# ProDocument_Schematics_2024-05-18.net
KiCad netlist of a schematic drawn in EasyEDA Pro
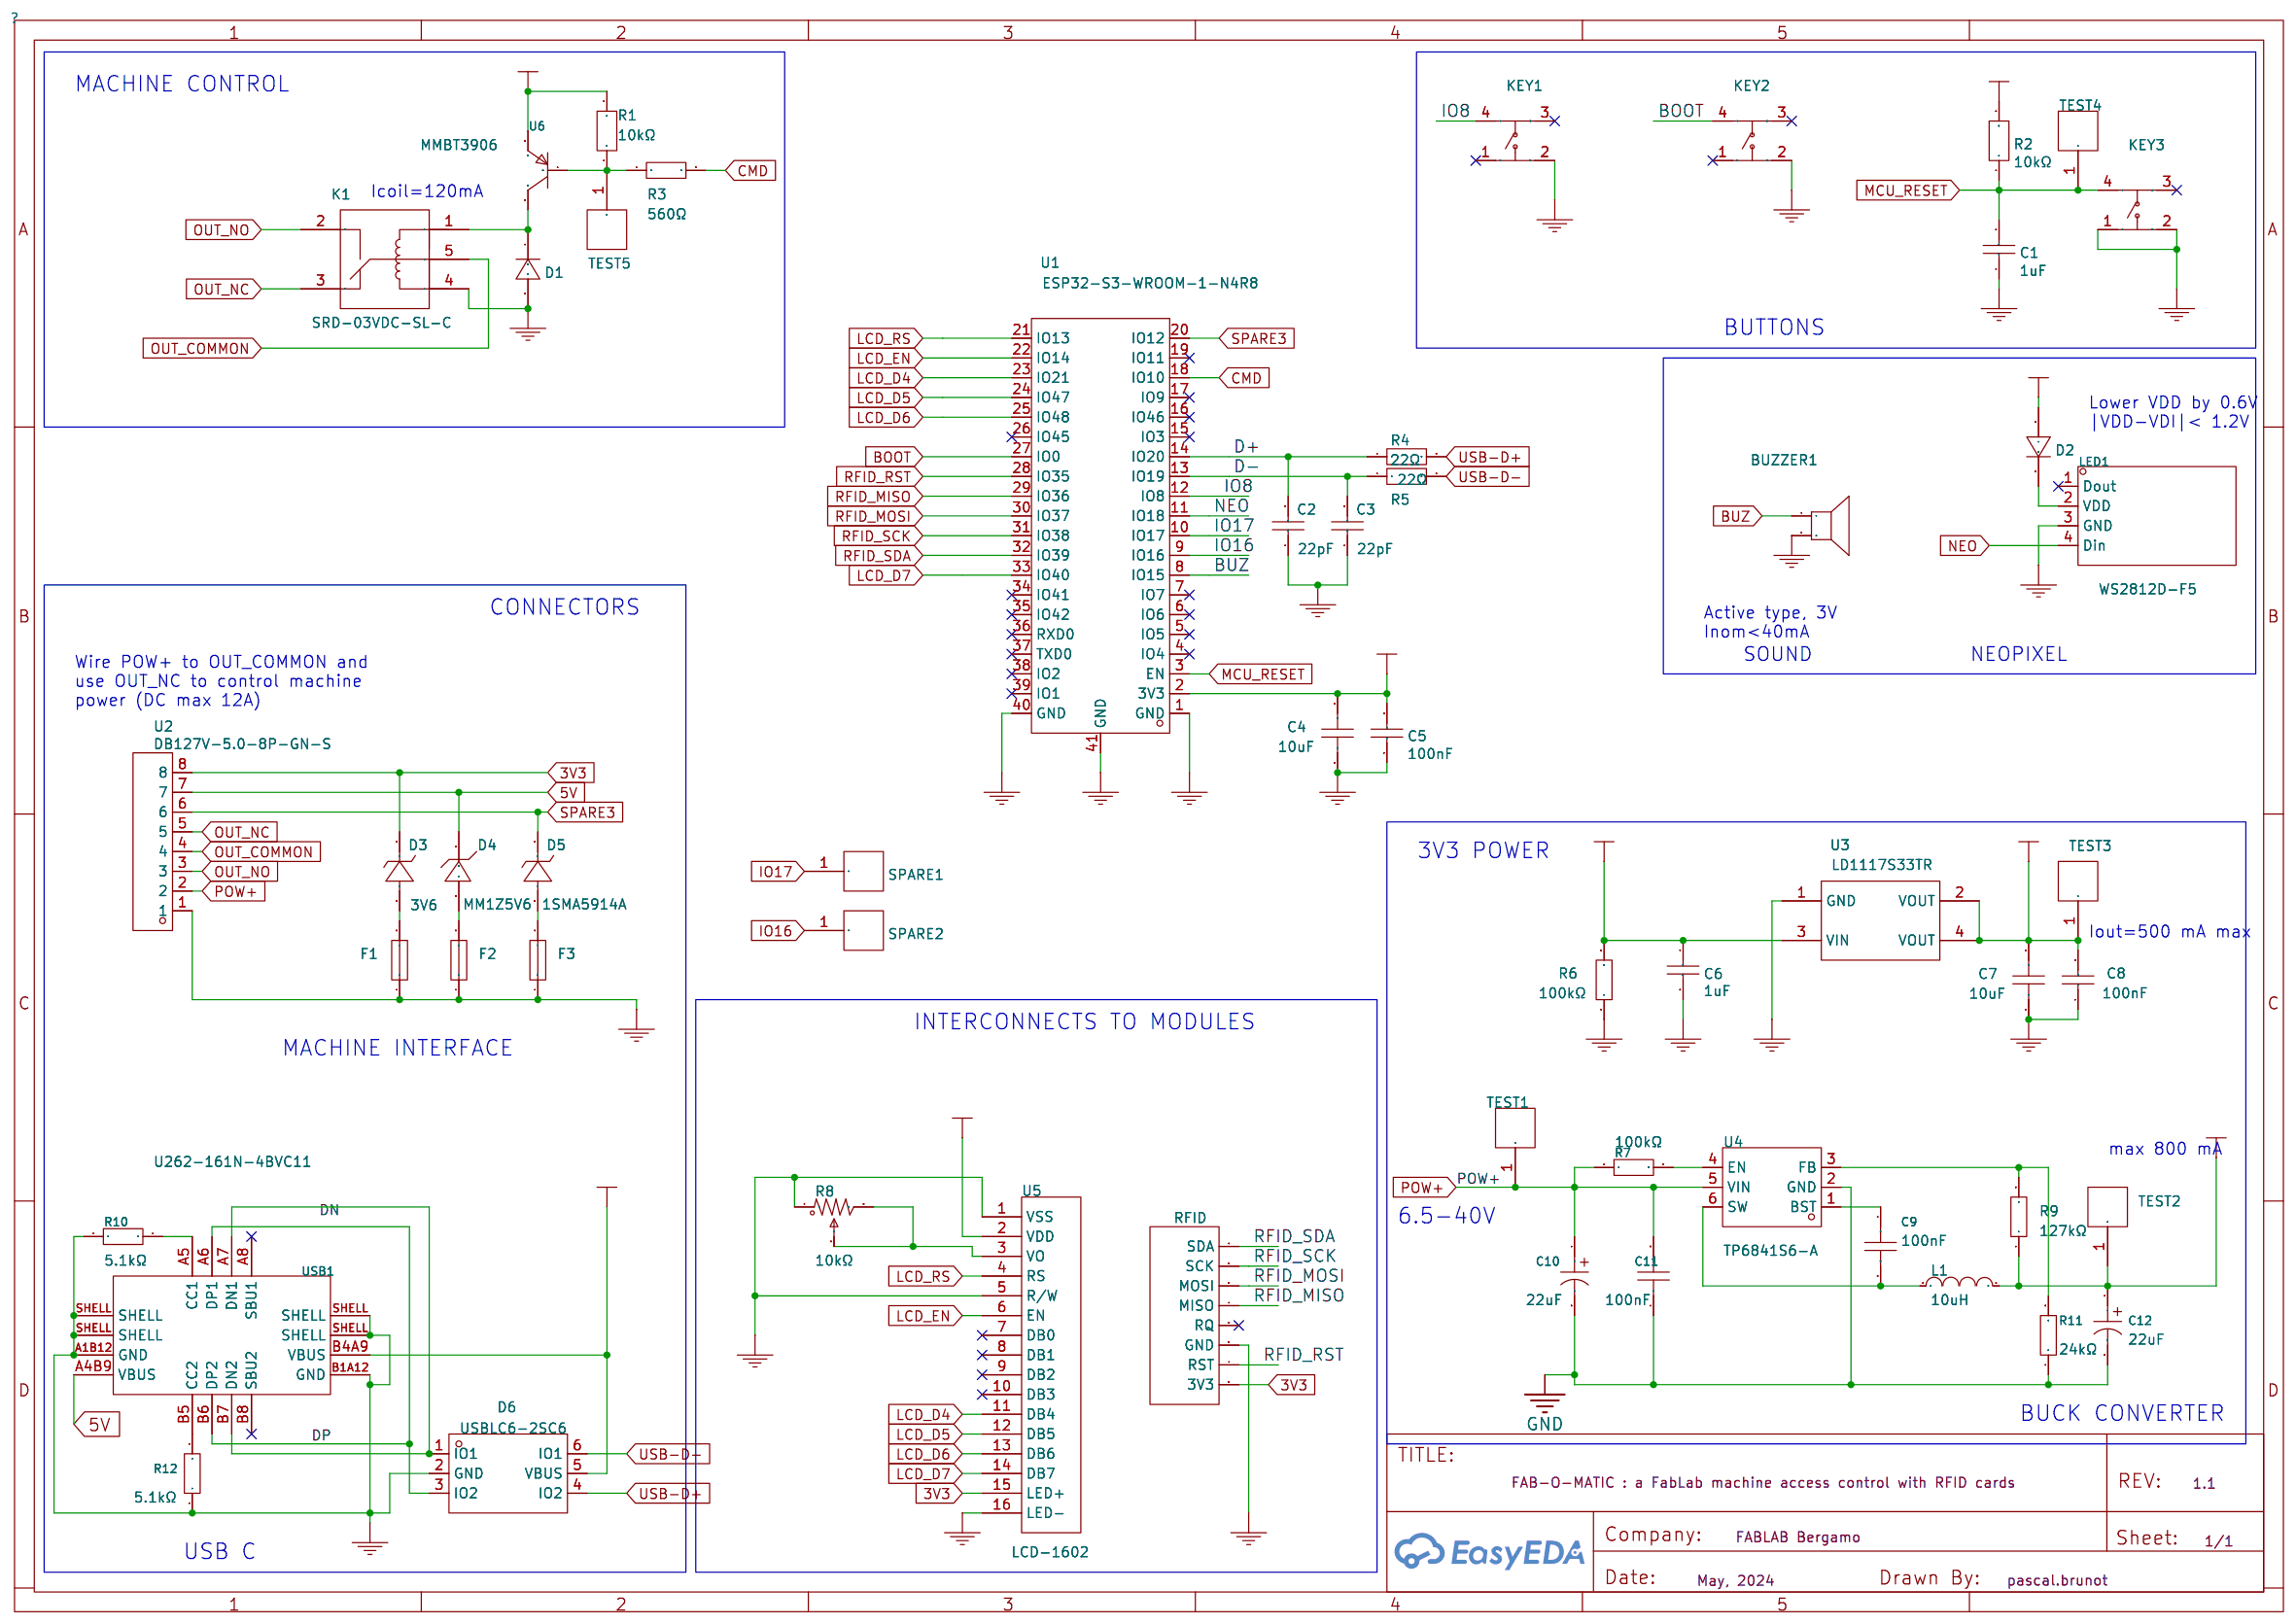
[diagram p0: schematic sheet]

(export (version "E")
  (design (tool "Eeschema 10.0.6"))
  (components
    (comp (ref "BUZZER1")
      (value "4kHz")
      (fields (field (name "Manufacturer Part") "SFN-12055PA6.5") (field (name "Manufacturer") "S&S(海旭)"))
      (libsource (lib "easyedapro") (part "4000Hz"))
    )
    (comp (ref "C1")
      (value "1uF")
      (fields
        (field (name "Manufacturer Part") "CL21B105KBFNNNE")
        (field (name "Manufacturer") "SAMSUNG(三星)")
      )
      (libsource (lib "easyedapro") (part "1uF"))
    )
    (comp (ref "C2")
      (value "22pF")
      (fields
        (field (name "Manufacturer Part") "CL10C220JB8NNNC")
        (field (name "Manufacturer") "SAMSUNG(三星)")
      )
      (libsource (lib "easyedapro") (part "22pF"))
    )
    (comp (ref "C3")
      (value "22pF")
      (fields
        (field (name "Manufacturer Part") "CL10C220JB8NNNC")
        (field (name "Manufacturer") "SAMSUNG(三星)")
      )
      (libsource (lib "easyedapro") (part "22pF"))
    )
    (comp (ref "C4")
      (value "10uF")
      (fields
        (field (name "Manufacturer Part") "GRM21BR61H106KE43L")
        (field (name "Manufacturer") "muRata(村田)")
      )
      (libsource (lib "easyedapro") (part "10uF"))
    )
    (comp (ref "C5")
      (value "100nF")
      (fields
        (field (name "Manufacturer Part") "CL21B104KCFNNNE")
        (field (name "Manufacturer") "SAMSUNG(三星)")
      )
      (libsource (lib "easyedapro") (part "100nF"))
    )
    (comp (ref "C6")
      (value "1uF")
      (fields
        (field (name "Manufacturer Part") "CL21B105KBFNNNE")
        (field (name "Manufacturer") "SAMSUNG(三星)")
      )
      (libsource (lib "easyedapro") (part "1uF"))
    )
    (comp (ref "C7")
      (value "10uF")
      (fields
        (field (name "Manufacturer Part") "GRM21BR61H106KE43L")
        (field (name "Manufacturer") "muRata(村田)")
      )
      (libsource (lib "easyedapro") (part "10uF"))
    )
    (comp (ref "C8")
      (value "100nF")
      (fields
        (field (name "Manufacturer Part") "CL21B104KCFNNNE")
        (field (name "Manufacturer") "SAMSUNG(三星)")
      )
      (libsource (lib "easyedapro") (part "100nF"))
    )
    (comp (ref "C9")
      (value "100nF")
      (footprint "easyedapro:C0603")
      (fields
        (field (name "Manufacturer Part") "CC0603KRX7R9BB104")
        (field (name "Manufacturer") "YAGEO(国巨)")
      )
      (libsource (lib "easyedapro") (part "CC0603KRX7R9BB104"))
    )
    (comp (ref "C10")
      (value "22uF")
      (footprint "easyedapro:CAP-SMD_BD6.3-L6.6-W6.6-FD")
      (fields
        (field (name "Manufacturer Part") "RVT22UF50V67RV0028")
        (field (name "Manufacturer") "KNSCHA(科尼盛)")
      )
      (libsource (lib "easyedapro") (part "RVT22UF50V67RV0028"))
    )
    (comp (ref "C11")
      (value "100nF")
      (footprint "easyedapro:C0603")
      (fields
        (field (name "Manufacturer Part") "CC0603KRX7R9BB104")
        (field (name "Manufacturer") "YAGEO(国巨)")
      )
      (libsource (lib "easyedapro") (part "CC0603KRX7R9BB104"))
    )
    (comp (ref "C12")
      (value "22uF")
      (footprint "easyedapro:CAP-SMD_BD6.3-L6.6-W6.6-FD")
      (fields
        (field (name "Manufacturer Part") "RVT22UF50V67RV0028")
        (field (name "Manufacturer") "KNSCHA(科尼盛)")
      )
      (libsource (lib "easyedapro") (part "RVT22UF50V67RV0028"))
    )
    (comp (ref "D1")
      (value "SM4007PL")
      (fields (field (name "Manufacturer") "MDD"))
      (libsource (lib "easyedapro") (part "SM4007PL"))
    )
    (comp (ref "D2")
      (value "SM4007PL")
      (fields (field (name "Manufacturer") "MDD"))
      (libsource (lib "easyedapro") (part "SM4007PL"))
    )
    (comp (ref "D3")
      (value "3V6")
      (fields (field (name "Manufacturer") "LGE(鲁光)"))
      (libsource (lib "easyedapro") (part "3V6"))
    )
    (comp (ref "D4")
      (value "MM1Z5V6")
      (fields (field (name "Manufacturer") "ST(先科)"))
      (libsource (lib "easyedapro") (part "5V6"))
    )
    (comp (ref "D5")
      (value "1SMA5914A")
      (fields (field (name "Manufacturer") "LGE(鲁光)"))
      (libsource (lib "easyedapro") (part "3V6"))
    )
    (comp (ref "D6")
      (value "USBLC6-2SC6")
      (fields (field (name "Manufacturer") "TECH PUBLIC(台舟)"))
      (libsource (lib "easyedapro") (part "USBLC6"))
    )
    (comp (ref "F1")
      (value "1206L016WR")
      (fields (field (name "Manufacturer") "Littelfuse(美国力特)"))
      (libsource (lib "easyedapro") (part "1206L016WR"))
    )
    (comp (ref "F2")
      (value "1206L016WR")
      (fields (field (name "Manufacturer") "Littelfuse(美国力特)"))
      (libsource (lib "easyedapro") (part "1206L016WR"))
    )
    (comp (ref "F3")
      (value "1206L016WR")
      (fields (field (name "Manufacturer") "Littelfuse(美国力特)"))
      (libsource (lib "easyedapro") (part "1206L016WR"))
    )
    (comp (ref "K1")
      (value "SRD-03VDC-SL-C")
      (fields (field (name "Manufacturer") "松乐"))
      (libsource (lib "easyedapro") (part "SRD-03VDC-SL-C_C496430"))
    )
    (comp (ref "KEY1")
      (value "TSA063G60-250")
      (footprint "easyedapro:KEY-SMD_4P-L6.1-W6.1-P4.50-LS9.0")
      (fields (field (name "Manufacturer") "BRIGHT(博瑞泰)"))
      (libsource (lib "easyedapro") (part "TSA063G60-250"))
    )
    (comp (ref "KEY2")
      (value "TSA063G60-250")
      (footprint "easyedapro:KEY-SMD_4P-L6.1-W6.1-P4.50-LS9.0")
      (fields (field (name "Manufacturer") "BRIGHT(博瑞泰)"))
      (libsource (lib "easyedapro") (part "TSA063G60-250"))
    )
    (comp (ref "KEY3")
      (value "TSA063G60-250")
      (footprint "easyedapro:KEY-SMD_4P-L6.1-W6.1-P4.50-LS9.0")
      (fields (field (name "Manufacturer") "BRIGHT(博瑞泰)"))
      (libsource (lib "easyedapro") (part "TSA063G60-250"))
    )
    (comp (ref "L1")
      (value "10uH")
      (footprint "easyedapro:IND-SMD_L4.0-W4.0")
      (fields (field (name "Manufacturer Part") "SWPA4030S100MT") (field (name "Manufacturer") "Sunlord(顺络)"))
      (libsource (lib "easyedapro") (part "SWPA4030S100MT"))
    )
    (comp (ref "LED1")
      (value "WS2812D-F5")
      (footprint "easyedapro:LED-TH_4P-BD5.8-P1.30")
      (description "Lamp Holder Type:5mm圆形灯头")
      (fields (field (name "Manufacturer") "worldsemi"))
      (libsource (lib "easyedapro") (part "WS2812D-F5"))
    )
    (comp (ref "P1")
      (value "RFID")
      (footprint "easyedapro:footprint_17af")
      (fields
        (field (name "Manufacturer Part") "Female headerHDR1X8-2.54")
        (field (name "Manufacturer") "BOOMELE")
      )
      (libsource (lib "easyedapro") (part "RFID"))
    )
    (comp (ref "R1")
      (value "10kΩ")
      (fields
        (field (name "Manufacturer Part") "0805W8F1002T5E")
        (field (name "Manufacturer") "UNI-ROYAL(厚声)")
      )
      (libsource (lib "easyedapro") (part "10k"))
    )
    (comp (ref "R2")
      (value "10kΩ")
      (fields
        (field (name "Manufacturer Part") "0805W8F1002T5E")
        (field (name "Manufacturer") "UNI-ROYAL(厚声)")
      )
      (libsource (lib "easyedapro") (part "10k"))
    )
    (comp (ref "R3")
      (value "560Ω")
      (fields
        (field (name "Manufacturer Part") "0805W8F5600T5E")
        (field (name "Manufacturer") "UNI-ROYAL(厚声)")
      )
      (libsource (lib "easyedapro") (part "560Ω"))
    )
    (comp (ref "R4")
      (value "22Ω")
      (fields
        (field (name "Manufacturer Part") "0603WAF220JT5E")
        (field (name "Manufacturer") "UNI-ROYAL(厚声)")
      )
      (libsource (lib "easyedapro") (part "22"))
    )
    (comp (ref "R5")
      (value "22Ω")
      (fields
        (field (name "Manufacturer Part") "0603WAF220JT5E")
        (field (name "Manufacturer") "UNI-ROYAL(厚声)")
      )
      (libsource (lib "easyedapro") (part "22"))
    )
    (comp (ref "R6")
      (value "100kΩ")
      (fields
        (field (name "Manufacturer Part") "0805W8F1003T5E")
        (field (name "Manufacturer") "UNI-ROYAL(厚声)")
      )
      (libsource (lib "easyedapro") (part "100kΩ"))
    )
    (comp (ref "R7")
      (value "100kΩ")
      (footprint "easyedapro:R0603")
      (fields
        (field (name "Manufacturer Part") "0603WAF1003T5E")
        (field (name "Manufacturer") "UNI-ROYAL(厚声)")
      )
      (libsource (lib "easyedapro") (part "0603WAF1003T5E"))
    )
    (comp (ref "R8")
      (value "10kΩ")
      (footprint "easyedapro:RES-ADJ-TH_3362P")
      (description "Resistance: Tolerance:±10% Tolerance:±10%")
      (fields (field (name "Manufacturer Part") "3362P-1-103") (field (name "Manufacturer") "BOCHEN(博晨)"))
      (libsource (lib "easyedapro") (part "3362P-1-103_C118956"))
    )
    (comp (ref "R9")
      (value "127kΩ")
      (footprint "easyedapro:R0603")
      (fields (field (name "Manufacturer Part") "RC0603FR-07127KL") (field (name "Manufacturer") "YAGEO(国巨)"))
      (libsource (lib "easyedapro") (part "RC0603FR-07127KL"))
    )
    (comp (ref "R10")
      (value "5.1kΩ")
      (footprint "easyedapro:R0603")
      (fields
        (field (name "Manufacturer Part") "0603WAF5101T5E")
        (field (name "Manufacturer") "UNI-ROYAL(厚声)")
      )
      (libsource (lib "easyedapro") (part "0603WAF5101T5E"))
    )
    (comp (ref "R11")
      (value "24kΩ")
      (footprint "easyedapro:R0603")
      (fields
        (field (name "Manufacturer Part") "0603WAF2402T5E")
        (field (name "Manufacturer") "UNI-ROYAL(厚声)")
      )
      (libsource (lib "easyedapro") (part "0603WAF2402T5E"))
    )
    (comp (ref "R12")
      (value "5.1kΩ")
      (footprint "easyedapro:R0603")
      (fields
        (field (name "Manufacturer Part") "0603WAF5101T5E")
        (field (name "Manufacturer") "UNI-ROYAL(厚声)")
      )
      (libsource (lib "easyedapro") (part "0603WAF5101T5E"))
    )
    (comp (ref "SPARE1")
      (value "0577-0-43-80-21-27-10-0")
      (footprint "easyedapro:footprint_662d")
      (libsource (lib "easyedapro") (part "0577-0-43-80-21-27-10-0"))
    )
    (comp (ref "SPARE2")
      (value "0577-0-43-80-21-27-10-0")
      (footprint "easyedapro:footprint_662d")
      (libsource (lib "easyedapro") (part "0577-0-43-80-21-27-10-0"))
    )
    (comp (ref "TEST1")
      (value "0577-0-43-80-21-27-10-0")
      (footprint "easyedapro:footprint_662d")
      (libsource (lib "easyedapro") (part "0577-0-43-80-21-27-10-0"))
    )
    (comp (ref "TEST2")
      (value "0577-0-43-80-21-27-10-0")
      (footprint "easyedapro:footprint_662d")
      (libsource (lib "easyedapro") (part "0577-0-43-80-21-27-10-0"))
    )
    (comp (ref "TEST3")
      (value "0577-0-43-80-21-27-10-0")
      (footprint "easyedapro:footprint_662d")
      (libsource (lib "easyedapro") (part "0577-0-43-80-21-27-10-0"))
    )
    (comp (ref "TEST4")
      (value "0577-0-43-80-21-27-10-0")
      (footprint "easyedapro:footprint_662d")
      (libsource (lib "easyedapro") (part "0577-0-43-80-21-27-10-0"))
    )
    (comp (ref "TEST5")
      (value "0577-0-43-80-21-27-10-0")
      (footprint "easyedapro:footprint_662d")
      (libsource (lib "easyedapro") (part "0577-0-43-80-21-27-10-0"))
    )
    (comp (ref "U1")
      (value "ESP32-S3-WROOM-1-N4R8")
      (fields (field (name "Manufacturer") "ESPRESSIF(乐鑫)"))
      (libsource (lib "easyedapro") (part "ESP32-S3-WROOM-1-N4"))
    )
    (comp (ref "U2")
      (value "DB127V-5.0-8P-GN-S")
      (fields (field (name "Manufacturer") "DORABO(地博电气)"))
      (libsource (lib "easyedapro") (part "DB127V-5.0-8P-GN-S"))
    )
    (comp (ref "U3")
      (value "LD1117S33TR")
      (fields (field (name "Manufacturer") "ST(意法半导体)"))
      (libsource (lib "easyedapro") (part "LD1117S33TR"))
    )
    (comp (ref "U4")
      (value "TP6841S6-A")
      (footprint "easyedapro:SOT-23-6_L2.9-W1.6-P0.95-LS2.8-BL")
      (fields (field (name "Manufacturer") "TECH PUBLIC(台舟)"))
      (libsource (lib "easyedapro") (part "TP6841S6-A"))
    )
    (comp (ref "U5")
      (value "LCD-1602")
      (footprint "easyedapro:footprint_8a57")
      (fields (field (name "Manufacturer Part") "?"))
      (libsource (lib "easyedapro") (part "LCD-1602"))
    )
    (comp (ref "U6")
      (value "MMBT3906")
      (footprint "easyedapro:SOT-23-3_L2.9-W1.3-P1.90-LS2.4-BR")
      (fields (field (name "Manufacturer") "宏迦橙"))
      (libsource (lib "easyedapro") (part "MMBT3906_C7420354"))
    )
    (comp (ref "USB1")
      (value "U262-161N-4BVC11")
      (footprint "easyedapro:USB-3.1-SMD_U262-161N-4BVC11")
      (fields (field (name "Manufacturer") "XKB Connectivity(中国星坤)"))
      (libsource (lib "easyedapro") (part "U262-16XN-4BVC11"))
    )
  )
  (nets
    (net (code "1") (name "/D+") (class "Default")
      (node (ref "C2") (pin "2") (pinfunction "2_2") (pintype "input"))
      (node (ref "R4") (pin "1") (pinfunction "1_1") (pintype "input"))
      (node (ref "U1") (pin "14") (pinfunction "IO20_14") (pintype "unspecified"))
    )
    (net (code "2") (name "/D-") (class "Default")
      (node (ref "C3") (pin "2") (pinfunction "2_2") (pintype "input"))
      (node (ref "R5") (pin "1") (pinfunction "1_1") (pintype "input"))
      (node (ref "U1") (pin "13") (pinfunction "IO19_13") (pintype "unspecified"))
    )
    (net (code "3") (name "/DN") (class "Default")
      (node (ref "D6") (pin "1") (pinfunction "IO1_1") (pintype "unspecified"))
      (node (ref "USB1") (pin "A7") (pinfunction "DN1_A7") (pintype "input"))
      (node (ref "USB1") (pin "B7") (pinfunction "DN2_B7") (pintype "input"))
    )
    (net (code "4") (name "/DP") (class "Default")
      (node (ref "D6") (pin "3") (pinfunction "IO2_3") (pintype "unspecified"))
      (node (ref "USB1") (pin "A6") (pinfunction "DP1_A6") (pintype "input"))
      (node (ref "USB1") (pin "B6") (pinfunction "DP2_B6") (pintype "input"))
    )
    (net (code "5") (name "/IO8") (class "Default")
      (node (ref "KEY1") (pin "4") (pinfunction "4_4") (pintype "input"))
      (node (ref "U1") (pin "12") (pinfunction "IO8_12") (pintype "unspecified"))
    )
    (net (code "6") (name "3V3") (class "Default")
      (node (ref "C4") (pin "2") (pinfunction "2_2") (pintype "unspecified"))
      (node (ref "C5") (pin "2") (pinfunction "2_2") (pintype "input"))
      (node (ref "C7") (pin "2") (pinfunction "2_2") (pintype "unspecified"))
      (node (ref "C8") (pin "2") (pinfunction "2_2") (pintype "input"))
      (node (ref "D3") (pin "1") (pinfunction "C_1") (pintype "unspecified"))
      (node (ref "P1") (pin "8") (pinfunction "3V3_8") (pintype "input"))
      (node (ref "R1") (pin "2") (pinfunction "2_2") (pintype "unspecified"))
      (node (ref "R2") (pin "2") (pinfunction "2_2") (pintype "unspecified"))
      (node (ref "TEST3") (pin "1") (pinfunction "1_1") (pintype "unspecified"))
      (node (ref "U1") (pin "2") (pinfunction "3V3_2") (pintype "unspecified"))
      (node (ref "U2") (pin "8") (pinfunction "8_8") (pintype "unspecified"))
      (node (ref "U3") (pin "2") (pinfunction "VOUT_2") (pintype "unspecified"))
      (node (ref "U3") (pin "4") (pinfunction "VOUT_4") (pintype "unspecified"))
      (node (ref "U5") (pin "15") (pinfunction "LED+_15") (pintype "unspecified"))
      (node (ref "U6") (pin "2") (pinfunction "E_2") (pintype "input"))
    )
    (net (code "7") (name "5V") (class "Default")
      (node (ref "C12") (pin "1") (pinfunction "1_1") (pintype "input"))
      (node (ref "C6") (pin "1") (pinfunction "1_1") (pintype "input"))
      (node (ref "D2") (pin "2") (pinfunction "A_2") (pintype "unspecified"))
      (node (ref "D4") (pin "1") (pinfunction "C_1") (pintype "unspecified"))
      (node (ref "D6") (pin "5") (pinfunction "VBUS_5") (pintype "unspecified"))
      (node (ref "L1") (pin "2") (pinfunction "2_2") (pintype "input"))
      (node (ref "R6") (pin "2") (pinfunction "2_2") (pintype "unspecified"))
      (node (ref "R9") (pin "1") (pinfunction "1_1") (pintype "unspecified"))
      (node (ref "TEST2") (pin "1") (pinfunction "1_1") (pintype "unspecified"))
      (node (ref "U2") (pin "7") (pinfunction "7_7") (pintype "unspecified"))
      (node (ref "U3") (pin "3") (pinfunction "VIN_3") (pintype "unspecified"))
      (node (ref "U5") (pin "2") (pinfunction "VDD_2") (pintype "unspecified"))
      (node (ref "USB1") (pin "A4B9") (pinfunction "VBUS_A4B9") (pintype "input"))
      (node (ref "USB1") (pin "B4A9") (pinfunction "VBUS_B4A9") (pintype "input"))
    )
    (net (code "8") (name "BOOT") (class "Default")
      (node (ref "KEY2") (pin "4") (pinfunction "4_4") (pintype "input"))
      (node (ref "U1") (pin "27") (pinfunction "IO0_27") (pintype "unspecified"))
    )
    (net (code "9") (name "BUZ") (class "Default")
      (node (ref "BUZZER1") (pin "1") (pinfunction "1_1") (pintype "unspecified"))
      (node (ref "U1") (pin "8") (pinfunction "IO15_8") (pintype "unspecified"))
    )
    (net (code "10") (name "CMD") (class "Default")
      (node (ref "R3") (pin "2") (pinfunction "2_2") (pintype "input"))
      (node (ref "U1") (pin "18") (pinfunction "IO10_18") (pintype "unspecified"))
    )
    (net (code "11") (name "GND") (class "Default")
      (node (ref "BUZZER1") (pin "2") (pinfunction "2_2") (pintype "unspecified"))
      (node (ref "C1") (pin "1") (pinfunction "1_1") (pintype "input"))
      (node (ref "C10") (pin "2") (pinfunction "2_2") (pintype "input"))
      (node (ref "C11") (pin "1") (pinfunction "1_1") (pintype "input"))
      (node (ref "C12") (pin "2") (pinfunction "2_2") (pintype "input"))
      (node (ref "C2") (pin "1") (pinfunction "1_1") (pintype "input"))
      (node (ref "C3") (pin "1") (pinfunction "1_1") (pintype "input"))
      (node (ref "C4") (pin "1") (pinfunction "1_1") (pintype "unspecified"))
      (node (ref "C5") (pin "1") (pinfunction "1_1") (pintype "input"))
      (node (ref "C6") (pin "2") (pinfunction "2_2") (pintype "input"))
      (node (ref "C7") (pin "1") (pinfunction "1_1") (pintype "unspecified"))
      (node (ref "C8") (pin "1") (pinfunction "1_1") (pintype "input"))
      (node (ref "D1") (pin "2") (pinfunction "A_2") (pintype "unspecified"))
      (node (ref "D6") (pin "2") (pinfunction "GND_2") (pintype "unspecified"))
      (node (ref "F1") (pin "1") (pinfunction "1_1") (pintype "unspecified"))
      (node (ref "F2") (pin "1") (pinfunction "1_1") (pintype "unspecified"))
      (node (ref "F3") (pin "1") (pinfunction "1_1") (pintype "unspecified"))
      (node (ref "K1") (pin "4") (pinfunction "4_4") (pintype "unspecified"))
      (node (ref "KEY1") (pin "2") (pinfunction "2_2") (pintype "input"))
      (node (ref "KEY2") (pin "2") (pinfunction "2_2") (pintype "input"))
      (node (ref "KEY3") (pin "1") (pinfunction "1_1") (pintype "input"))
      (node (ref "KEY3") (pin "2") (pinfunction "2_2") (pintype "input"))
      (node (ref "LED1") (pin "3") (pinfunction "GND_3") (pintype "input"))
      (node (ref "P1") (pin "6") (pinfunction "GND_6") (pintype "input"))
      (node (ref "R10") (pin "2") (pinfunction "2_2") (pintype "input"))
      (node (ref "R11") (pin "1") (pinfunction "1_1") (pintype "input"))
      (node (ref "R12") (pin "1") (pinfunction "1_1") (pintype "input"))
      (node (ref "R6") (pin "1") (pinfunction "1_1") (pintype "unspecified"))
      (node (ref "R8") (pin "1") (pinfunction "1_1") (pintype "input"))
      (node (ref "U1") (pin "1") (pinfunction "GND_1") (pintype "unspecified"))
      (node (ref "U1") (pin "40") (pinfunction "GND_40") (pintype "unspecified"))
      (node (ref "U1") (pin "41") (pinfunction "GND_41") (pintype "unspecified"))
      (node (ref "U2") (pin "1") (pinfunction "1_1") (pintype "unspecified"))
      (node (ref "U3") (pin "1") (pinfunction "GND_1") (pintype "unspecified"))
      (node (ref "U4") (pin "2") (pinfunction "GND_2") (pintype "input"))
      (node (ref "U5") (pin "1") (pinfunction "VSS_1") (pintype "unspecified"))
      (node (ref "U5") (pin "16") (pinfunction "LED-_16") (pintype "unspecified"))
      (node (ref "U5") (pin "5") (pinfunction "R/W_5") (pintype "unspecified"))
      (node (ref "USB1") (pin "A1B12") (pinfunction "GND_A1B12") (pintype "input"))
      (node (ref "USB1") (pin "B1A12") (pinfunction "GND_B1A12") (pintype "input"))
      (node (ref "USB1") (pin "SHELL") (pinfunction "SHELL_SHELL") (pintype "input"))
    )
    (net (code "12") (name "IO16") (class "Default")
      (node (ref "SPARE2") (pin "1") (pinfunction "1_1") (pintype "unspecified"))
      (node (ref "U1") (pin "9") (pinfunction "IO16_9") (pintype "unspecified"))
    )
    (net (code "13") (name "IO17") (class "Default")
      (node (ref "SPARE1") (pin "1") (pinfunction "1_1") (pintype "unspecified"))
      (node (ref "U1") (pin "10") (pinfunction "IO17_10") (pintype "unspecified"))
    )
    (net (code "14") (name "LCD_D4") (class "Default")
      (node (ref "U1") (pin "23") (pinfunction "IO21_23") (pintype "unspecified"))
      (node (ref "U5") (pin "11") (pinfunction "DB4_11") (pintype "unspecified"))
    )
    (net (code "15") (name "LCD_D5") (class "Default")
      (node (ref "U1") (pin "24") (pinfunction "IO47_24") (pintype "unspecified"))
      (node (ref "U5") (pin "12") (pinfunction "DB5_12") (pintype "unspecified"))
    )
    (net (code "16") (name "LCD_D6") (class "Default")
      (node (ref "U1") (pin "25") (pinfunction "IO48_25") (pintype "unspecified"))
      (node (ref "U5") (pin "13") (pinfunction "DB6_13") (pintype "unspecified"))
    )
    (net (code "17") (name "LCD_D7") (class "Default")
      (node (ref "U1") (pin "33") (pinfunction "IO40_33") (pintype "unspecified"))
      (node (ref "U5") (pin "14") (pinfunction "DB7_14") (pintype "unspecified"))
    )
    (net (code "18") (name "LCD_EN") (class "Default")
      (node (ref "U1") (pin "22") (pinfunction "IO14_22") (pintype "unspecified"))
      (node (ref "U5") (pin "6") (pinfunction "EN_6") (pintype "unspecified"))
    )
    (net (code "19") (name "LCD_RS") (class "Default")
      (node (ref "U1") (pin "21") (pinfunction "IO13_21") (pintype "unspecified"))
      (node (ref "U5") (pin "4") (pinfunction "RS_4") (pintype "unspecified"))
    )
    (net (code "20") (name "MCU_RESET") (class "Default")
      (node (ref "C1") (pin "2") (pinfunction "2_2") (pintype "input"))
      (node (ref "KEY3") (pin "4") (pinfunction "4_4") (pintype "input"))
      (node (ref "R2") (pin "1") (pinfunction "1_1") (pintype "unspecified"))
      (node (ref "TEST4") (pin "1") (pinfunction "1_1") (pintype "unspecified"))
      (node (ref "U1") (pin "3") (pinfunction "EN_3") (pintype "unspecified"))
    )
    (net (code "21") (name "NEO") (class "Default")
      (node (ref "LED1") (pin "4") (pinfunction "Din_4") (pintype "input"))
      (node (ref "U1") (pin "11") (pinfunction "IO18_11") (pintype "unspecified"))
    )
    (net (code "22") (name "Net-(D1-C)") (class "Default")
      (node (ref "D1") (pin "1") (pinfunction "C_1") (pintype "unspecified"))
      (node (ref "K1") (pin "1") (pinfunction "1_1") (pintype "unspecified"))
      (node (ref "U6") (pin "3") (pinfunction "C_3") (pintype "input"))
    )
    (net (code "23") (name "Net-(D2-C)") (class "Default")
      (node (ref "D2") (pin "1") (pinfunction "C_1") (pintype "unspecified"))
      (node (ref "LED1") (pin "2") (pinfunction "VDD_2") (pintype "input"))
    )
    (net (code "24") (name "Net-(D3-A)") (class "Default")
      (node (ref "D3") (pin "2") (pinfunction "A_2") (pintype "unspecified"))
      (node (ref "F1") (pin "2") (pinfunction "2_2") (pintype "unspecified"))
    )
    (net (code "25") (name "Net-(D4-A)") (class "Default")
      (node (ref "D4") (pin "2") (pinfunction "A_2") (pintype "unspecified"))
      (node (ref "F2") (pin "2") (pinfunction "2_2") (pintype "unspecified"))
    )
    (net (code "26") (name "Net-(D5-A)") (class "Default")
      (node (ref "D5") (pin "2") (pinfunction "A_2") (pintype "unspecified"))
      (node (ref "F3") (pin "2") (pinfunction "2_2") (pintype "unspecified"))
    )
    (net (code "27") (name "Net-(U4-BST)") (class "Default")
      (node (ref "C9") (pin "1") (pinfunction "1_1") (pintype "input"))
      (node (ref "U4") (pin "1") (pinfunction "BST_1") (pintype "input"))
    )
    (net (code "28") (name "Net-(U4-EN)") (class "Default")
      (node (ref "R7") (pin "2") (pinfunction "2_2") (pintype "input"))
      (node (ref "U4") (pin "4") (pinfunction "EN_4") (pintype "input"))
    )
    (net (code "29") (name "Net-(U4-FB)") (class "Default")
      (node (ref "R11") (pin "2") (pinfunction "2_2") (pintype "input"))
      (node (ref "R9") (pin "2") (pinfunction "2_2") (pintype "unspecified"))
      (node (ref "U4") (pin "3") (pinfunction "FB_3") (pintype "input"))
    )
    (net (code "30") (name "Net-(U4-SW)") (class "Default")
      (node (ref "C9") (pin "2") (pinfunction "2_2") (pintype "input"))
      (node (ref "L1") (pin "1") (pinfunction "1_1") (pintype "input"))
      (node (ref "U4") (pin "6") (pinfunction "SW_6") (pintype "input"))
    )
    (net (code "31") (name "Net-(U5-VO)") (class "Default")
      (node (ref "R8") (pin "2") (pinfunction "2_2") (pintype "input"))
      (node (ref "R8") (pin "3") (pinfunction "3_3") (pintype "input"))
      (node (ref "U5") (pin "3") (pinfunction "VO_3") (pintype "unspecified"))
    )
    (net (code "32") (name "Net-(U6-B)") (class "Default")
      (node (ref "R1") (pin "1") (pinfunction "1_1") (pintype "unspecified"))
      (node (ref "R3") (pin "1") (pinfunction "1_1") (pintype "input"))
      (node (ref "TEST5") (pin "1") (pinfunction "1_1") (pintype "unspecified"))
      (node (ref "U6") (pin "1") (pinfunction "B_1") (pintype "input"))
    )
    (net (code "33") (name "Net-(USB1-CC1)") (class "Default")
      (node (ref "R10") (pin "1") (pinfunction "1_1") (pintype "input"))
      (node (ref "USB1") (pin "A5") (pinfunction "CC1_A5") (pintype "input"))
    )
    (net (code "34") (name "Net-(USB1-CC2)") (class "Default")
      (node (ref "R12") (pin "2") (pinfunction "2_2") (pintype "input"))
      (node (ref "USB1") (pin "B5") (pinfunction "CC2_B5") (pintype "input"))
    )
    (net (code "35") (name "OUT_COMMON") (class "Default")
      (node (ref "K1") (pin "5") (pinfunction "5_5") (pintype "unspecified"))
      (node (ref "U2") (pin "4") (pinfunction "4_4") (pintype "unspecified"))
    )
    (net (code "36") (name "OUT_NC") (class "Default")
      (node (ref "K1") (pin "3") (pinfunction "3_3") (pintype "unspecified"))
      (node (ref "U2") (pin "5") (pinfunction "5_5") (pintype "unspecified"))
    )
    (net (code "37") (name "OUT_NO") (class "Default")
      (node (ref "K1") (pin "2") (pinfunction "2_2") (pintype "unspecified"))
      (node (ref "U2") (pin "3") (pinfunction "3_3") (pintype "unspecified"))
    )
    (net (code "38") (name "POW+") (class "Default")
      (node (ref "C10") (pin "1") (pinfunction "1_1") (pintype "input"))
      (node (ref "C11") (pin "2") (pinfunction "2_2") (pintype "input"))
      (node (ref "R7") (pin "1") (pinfunction "1_1") (pintype "input"))
      (node (ref "TEST1") (pin "1") (pinfunction "1_1") (pintype "unspecified"))
      (node (ref "U2") (pin "2") (pinfunction "2_2") (pintype "unspecified"))
      (node (ref "U4") (pin "5") (pinfunction "VIN_5") (pintype "input"))
    )
    (net (code "39") (name "RFID_MISO") (class "Default")
      (node (ref "P1") (pin "4") (pinfunction "MISO_4") (pintype "input"))
      (node (ref "U1") (pin "29") (pinfunction "IO36_29") (pintype "unspecified"))
    )
    (net (code "40") (name "RFID_MOSI") (class "Default")
      (node (ref "P1") (pin "3") (pinfunction "MOSI_3") (pintype "input"))
      (node (ref "U1") (pin "30") (pinfunction "IO37_30") (pintype "unspecified"))
    )
    (net (code "41") (name "RFID_RST") (class "Default")
      (node (ref "P1") (pin "7") (pinfunction "RST_7") (pintype "input"))
      (node (ref "U1") (pin "28") (pinfunction "IO35_28") (pintype "unspecified"))
    )
    (net (code "42") (name "RFID_SCK") (class "Default")
      (node (ref "P1") (pin "2") (pinfunction "SCK_2") (pintype "input"))
      (node (ref "U1") (pin "31") (pinfunction "IO38_31") (pintype "unspecified"))
    )
    (net (code "43") (name "RFID_SDA") (class "Default")
      (node (ref "P1") (pin "1") (pinfunction "SDA_1") (pintype "input"))
      (node (ref "U1") (pin "32") (pinfunction "IO39_32") (pintype "unspecified"))
    )
    (net (code "44") (name "SPARE3") (class "Default")
      (node (ref "D5") (pin "1") (pinfunction "C_1") (pintype "unspecified"))
      (node (ref "U1") (pin "20") (pinfunction "IO12_20") (pintype "unspecified"))
      (node (ref "U2") (pin "6") (pinfunction "6_6") (pintype "unspecified"))
    )
    (net (code "45") (name "USB-D+") (class "Default")
      (node (ref "D6") (pin "4") (pinfunction "IO2_4") (pintype "unspecified"))
      (node (ref "R4") (pin "2") (pinfunction "2_2") (pintype "input"))
    )
    (net (code "46") (name "USB-D-") (class "Default")
      (node (ref "D6") (pin "6") (pinfunction "IO1_6") (pintype "unspecified"))
      (node (ref "R5") (pin "2") (pinfunction "2_2") (pintype "input"))
    )
    (net (code "47") (name "unconnected-(KEY1-Pad1)") (class "Default")
      (node (ref "KEY1") (pin "1") (pinfunction "1_1") (pintype "input+no_connect"))
    )
    (net (code "48") (name "unconnected-(KEY1-Pad3)") (class "Default")
      (node (ref "KEY1") (pin "3") (pinfunction "3_3") (pintype "input+no_connect"))
    )
    (net (code "49") (name "unconnected-(KEY2-Pad1)") (class "Default")
      (node (ref "KEY2") (pin "1") (pinfunction "1_1") (pintype "input+no_connect"))
    )
    (net (code "50") (name "unconnected-(KEY2-Pad3)") (class "Default")
      (node (ref "KEY2") (pin "3") (pinfunction "3_3") (pintype "input+no_connect"))
    )
    (net (code "51") (name "unconnected-(KEY3-Pad3)") (class "Default")
      (node (ref "KEY3") (pin "3") (pinfunction "3_3") (pintype "input+no_connect"))
    )
    (net (code "52") (name "unconnected-(LED1-Dout-Pad1)") (class "Default")
      (node (ref "LED1") (pin "1") (pinfunction "Dout_1") (pintype "input+no_connect"))
    )
    (net (code "53") (name "unconnected-(P1-RQ-Pad5)") (class "Default")
      (node (ref "P1") (pin "5") (pinfunction "RQ_5") (pintype "input+no_connect"))
    )
    (net (code "54") (name "unconnected-(U1-IO1-Pad39)") (class "Default")
      (node (ref "U1") (pin "39") (pinfunction "IO1_39") (pintype "unspecified+no_connect"))
    )
    (net (code "55") (name "unconnected-(U1-IO2-Pad38)") (class "Default")
      (node (ref "U1") (pin "38") (pinfunction "IO2_38") (pintype "unspecified+no_connect"))
    )
    (net (code "56") (name "unconnected-(U1-IO3-Pad15)") (class "Default")
      (node (ref "U1") (pin "15") (pinfunction "IO3_15") (pintype "unspecified+no_connect"))
    )
    (net (code "57") (name "unconnected-(U1-IO4-Pad4)") (class "Default")
      (node (ref "U1") (pin "4") (pinfunction "IO4_4") (pintype "unspecified+no_connect"))
    )
    (net (code "58") (name "unconnected-(U1-IO5-Pad5)") (class "Default")
      (node (ref "U1") (pin "5") (pinfunction "IO5_5") (pintype "unspecified+no_connect"))
    )
    (net (code "59") (name "unconnected-(U1-IO6-Pad6)") (class "Default")
      (node (ref "U1") (pin "6") (pinfunction "IO6_6") (pintype "unspecified+no_connect"))
    )
    (net (code "60") (name "unconnected-(U1-IO7-Pad7)") (class "Default")
      (node (ref "U1") (pin "7") (pinfunction "IO7_7") (pintype "unspecified+no_connect"))
    )
    (net (code "61") (name "unconnected-(U1-IO9-Pad17)") (class "Default")
      (node (ref "U1") (pin "17") (pinfunction "IO9_17") (pintype "unspecified+no_connect"))
    )
    (net (code "62") (name "unconnected-(U1-IO11-Pad19)") (class "Default")
      (node (ref "U1") (pin "19") (pinfunction "IO11_19") (pintype "unspecified+no_connect"))
    )
    (net (code "63") (name "unconnected-(U1-IO41-Pad34)") (class "Default")
      (node (ref "U1") (pin "34") (pinfunction "IO41_34") (pintype "unspecified+no_connect"))
    )
    (net (code "64") (name "unconnected-(U1-IO42-Pad35)") (class "Default")
      (node (ref "U1") (pin "35") (pinfunction "IO42_35") (pintype "unspecified+no_connect"))
    )
    (net (code "65") (name "unconnected-(U1-IO45-Pad26)") (class "Default")
      (node (ref "U1") (pin "26") (pinfunction "IO45_26") (pintype "unspecified+no_connect"))
    )
    (net (code "66") (name "unconnected-(U1-IO46-Pad16)") (class "Default")
      (node (ref "U1") (pin "16") (pinfunction "IO46_16") (pintype "unspecified+no_connect"))
    )
    (net (code "67") (name "unconnected-(U1-RXD0-Pad36)") (class "Default")
      (node (ref "U1") (pin "36") (pinfunction "RXD0_36") (pintype "unspecified+no_connect"))
    )
    (net (code "68") (name "unconnected-(U1-TXD0-Pad37)") (class "Default")
      (node (ref "U1") (pin "37") (pinfunction "TXD0_37") (pintype "unspecified+no_connect"))
    )
    (net (code "69") (name "unconnected-(U5-DB0-Pad7)") (class "Default")
      (node (ref "U5") (pin "7") (pinfunction "DB0_7") (pintype "unspecified+no_connect"))
    )
    (net (code "70") (name "unconnected-(U5-DB1-Pad8)") (class "Default")
      (node (ref "U5") (pin "8") (pinfunction "DB1_8") (pintype "unspecified+no_connect"))
    )
    (net (code "71") (name "unconnected-(U5-DB2-Pad9)") (class "Default")
      (node (ref "U5") (pin "9") (pinfunction "DB2_9") (pintype "unspecified+no_connect"))
    )
    (net (code "72") (name "unconnected-(U5-DB3-Pad10)") (class "Default")
      (node (ref "U5") (pin "10") (pinfunction "DB3_10") (pintype "unspecified+no_connect"))
    )
    (net (code "73") (name "unconnected-(USB1-SBU1-PadA8)") (class "Default")
      (node (ref "USB1") (pin "A8") (pinfunction "SBU1_A8") (pintype "input+no_connect"))
    )
    (net (code "74") (name "unconnected-(USB1-SBU2-PadB8)") (class "Default")
      (node (ref "USB1") (pin "B8") (pinfunction "SBU2_B8") (pintype "input+no_connect"))
    )
  )
)
